# CONNECTEUR_3.net
KiCad netlist of a schematic drawn in Altium Designer
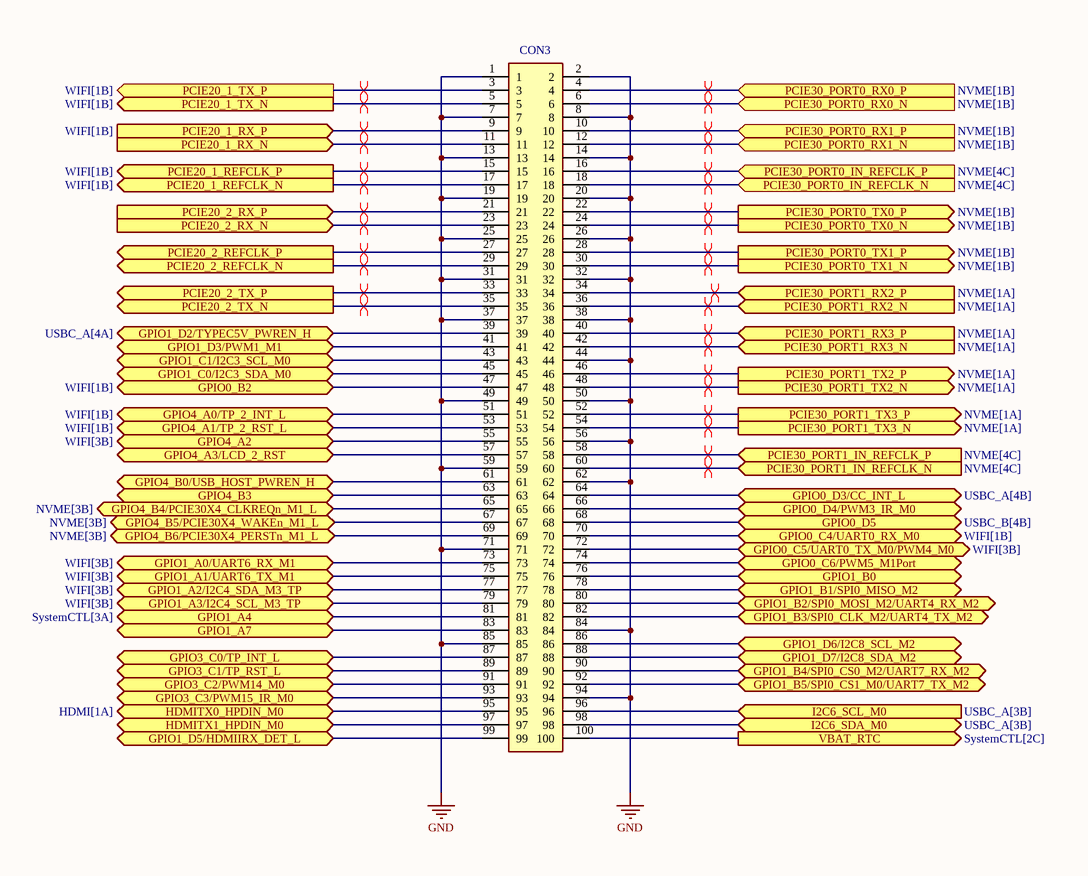
[diagram p0: CONNECTEUR_3.SchDoc, right]

(export (version "E")
  (design (tool "Eeschema 10.0.6"))
  (components
    (comp (ref "CON3")
      (value "DF40HC")
      (footprint "SamacSys:DF40HC30100DS04V51")
      (description "Stacking Board Connector, DF40 Series, Receptacle, 0.4 mm, 100, Surface Mount, G")
      (fields
        (field (name "MANUFACTURER_PART_NUMBER") "DF40HC(3.0)-100DS-0.4V(51")
        (field (name "MOUSER PART NUMBER") "798-DF40HC30100DS451")
      )
      (libsource (lib "SamacSys") (part "DF40HC(3.0)-100DS-0.4V(51)"))
    )
  )
  (nets
    (net (code "1") (name "/GPIO0_B2") (class "Default")
      (node (ref "CON3") (pin "47") (pinfunction "47_47") (pintype "passive"))
    )
    (net (code "2") (name "/GPIO0_C4{slash}UART0_RX_M0") (class "Default")
      (node (ref "CON3") (pin "70") (pinfunction "70_70") (pintype "passive"))
    )
    (net (code "3") (name "/GPIO0_C5{slash}UART0_TX_M0{slash}PWM4_M0") (class "Default")
      (node (ref "CON3") (pin "72") (pinfunction "72_72") (pintype "passive"))
    )
    (net (code "4") (name "/GPIO0_C6{slash}PWM5_M1Port") (class "Default")
      (node (ref "CON3") (pin "74") (pinfunction "74_74") (pintype "passive"))
    )
    (net (code "5") (name "/GPIO0_D3{slash}CC_INT_L") (class "Default")
      (node (ref "CON3") (pin "64") (pinfunction "64_64") (pintype "passive"))
    )
    (net (code "6") (name "/GPIO0_D4{slash}PWM3_IR_M0") (class "Default")
      (node (ref "CON3") (pin "66") (pinfunction "66_66") (pintype "passive"))
    )
    (net (code "7") (name "/GPIO0_D5") (class "Default")
      (node (ref "CON3") (pin "68") (pinfunction "68_68") (pintype "passive"))
    )
    (net (code "8") (name "/GPIO1_A0{slash}UART6_RX_M1") (class "Default")
      (node (ref "CON3") (pin "73") (pinfunction "73_73") (pintype "passive"))
    )
    (net (code "9") (name "/GPIO1_A1{slash}UART6_TX_M1") (class "Default")
      (node (ref "CON3") (pin "75") (pinfunction "75_75") (pintype "passive"))
    )
    (net (code "10") (name "/GPIO1_A2{slash}I2C4_SDA_M3_TP") (class "Default")
      (node (ref "CON3") (pin "77") (pinfunction "77_77") (pintype "passive"))
    )
    (net (code "11") (name "/GPIO1_A3{slash}I2C4_SCL_M3_TP") (class "Default")
      (node (ref "CON3") (pin "79") (pinfunction "79_79") (pintype "passive"))
    )
    (net (code "12") (name "/GPIO1_A4") (class "Default")
      (node (ref "CON3") (pin "81") (pinfunction "81_81") (pintype "passive"))
    )
    (net (code "13") (name "/GPIO1_A7") (class "Default")
      (node (ref "CON3") (pin "83") (pinfunction "83_83") (pintype "passive"))
    )
    (net (code "14") (name "/GPIO1_B0") (class "Default")
      (node (ref "CON3") (pin "76") (pinfunction "76_76") (pintype "passive"))
    )
    (net (code "15") (name "/GPIO1_B1{slash}SPI0_MISO_M2") (class "Default")
      (node (ref "CON3") (pin "78") (pinfunction "78_78") (pintype "passive"))
    )
    (net (code "16") (name "/GPIO1_B2{slash}SPI0_MOSI_M2{slash}UART4_RX_M2") (class "Default")
      (node (ref "CON3") (pin "80") (pinfunction "80_80") (pintype "passive"))
    )
    (net (code "17") (name "/GPIO1_B3{slash}SPI0_CLK_M2{slash}UART4_TX_M2") (class "Default")
      (node (ref "CON3") (pin "82") (pinfunction "82_82") (pintype "passive"))
    )
    (net (code "18") (name "/GPIO1_B4{slash}SPI0_CS0_M2{slash}UART7_RX_M2") (class "Default")
      (node (ref "CON3") (pin "90") (pinfunction "90_90") (pintype "passive"))
    )
    (net (code "19") (name "/GPIO1_B5{slash}SPI0_CS1_M0{slash}UART7_TX_M2") (class "Default")
      (node (ref "CON3") (pin "92") (pinfunction "92_92") (pintype "passive"))
    )
    (net (code "20") (name "/GPIO1_C0{slash}I2C3_SDA_M0") (class "Default")
      (node (ref "CON3") (pin "45") (pinfunction "45_45") (pintype "passive"))
    )
    (net (code "21") (name "/GPIO1_C1{slash}I2C3_SCL_M0") (class "Default")
      (node (ref "CON3") (pin "43") (pinfunction "43_43") (pintype "passive"))
    )
    (net (code "22") (name "/GPIO1_D2{slash}TYPEC5V_PWREN_H") (class "Default")
      (node (ref "CON3") (pin "39") (pinfunction "39_39") (pintype "passive"))
    )
    (net (code "23") (name "/GPIO1_D3{slash}PWM1_M1") (class "Default")
      (node (ref "CON3") (pin "41") (pinfunction "41_41") (pintype "passive"))
    )
    (net (code "24") (name "/GPIO1_D5{slash}HDMIIRX_DET_L") (class "Default")
      (node (ref "CON3") (pin "99") (pinfunction "99_99") (pintype "passive"))
    )
    (net (code "25") (name "/GPIO1_D6{slash}I2C8_SCL_M2") (class "Default")
      (node (ref "CON3") (pin "86") (pinfunction "86_86") (pintype "passive"))
    )
    (net (code "26") (name "/GPIO1_D7{slash}I2C8_SDA_M2") (class "Default")
      (node (ref "CON3") (pin "88") (pinfunction "88_88") (pintype "passive"))
    )
    (net (code "27") (name "/GPIO3_C0{slash}TP_INT_L") (class "Default")
      (node (ref "CON3") (pin "87") (pinfunction "87_87") (pintype "passive"))
    )
    (net (code "28") (name "/GPIO3_C1{slash}TP_RST_L") (class "Default")
      (node (ref "CON3") (pin "89") (pinfunction "89_89") (pintype "passive"))
    )
    (net (code "29") (name "/GPIO3_C2{slash}PWM14_M0") (class "Default")
      (node (ref "CON3") (pin "91") (pinfunction "91_91") (pintype "passive"))
    )
    (net (code "30") (name "/GPIO3_C3{slash}PWM15_IR_M0") (class "Default")
      (node (ref "CON3") (pin "93") (pinfunction "93_93") (pintype "passive"))
    )
    (net (code "31") (name "/GPIO4_A0{slash}TP_2_INT_L") (class "Default")
      (node (ref "CON3") (pin "51") (pinfunction "51_51") (pintype "passive"))
    )
    (net (code "32") (name "/GPIO4_A1{slash}TP_2_RST_L") (class "Default")
      (node (ref "CON3") (pin "53") (pinfunction "53_53") (pintype "passive"))
    )
    (net (code "33") (name "/GPIO4_A2") (class "Default")
      (node (ref "CON3") (pin "55") (pinfunction "55_55") (pintype "passive"))
    )
    (net (code "34") (name "/GPIO4_A3{slash}LCD_2_RST") (class "Default")
      (node (ref "CON3") (pin "57") (pinfunction "57_57") (pintype "passive"))
    )
    (net (code "35") (name "/GPIO4_B0{slash}USB_HOST_PWREN_H") (class "Default")
      (node (ref "CON3") (pin "61") (pinfunction "61_61") (pintype "passive"))
    )
    (net (code "36") (name "/GPIO4_B3") (class "Default")
      (node (ref "CON3") (pin "63") (pinfunction "63_63") (pintype "passive"))
    )
    (net (code "37") (name "/GPIO4_B4{slash}PCIE30X4_CLKREQn_M1_L") (class "Default")
      (node (ref "CON3") (pin "65") (pinfunction "65_65") (pintype "passive"))
    )
    (net (code "38") (name "/GPIO4_B5{slash}PCIE30X4_WAKEn_M1_L") (class "Default")
      (node (ref "CON3") (pin "67") (pinfunction "67_67") (pintype "passive"))
    )
    (net (code "39") (name "/GPIO4_B6{slash}PCIE30X4_PERSTn_M1_L") (class "Default")
      (node (ref "CON3") (pin "69") (pinfunction "69_69") (pintype "passive"))
    )
    (net (code "40") (name "/HDMITX0_HPDIN_M0") (class "Default")
      (node (ref "CON3") (pin "95") (pinfunction "95_95") (pintype "passive"))
    )
    (net (code "41") (name "/HDMITX1_HPDIN_M0") (class "Default")
      (node (ref "CON3") (pin "97") (pinfunction "97_97") (pintype "passive"))
    )
    (net (code "42") (name "/I2C6_SCL_M0") (class "Default")
      (node (ref "CON3") (pin "96") (pinfunction "96_96") (pintype "passive"))
    )
    (net (code "43") (name "/I2C6_SDA_M0") (class "Default")
      (node (ref "CON3") (pin "98") (pinfunction "98_98") (pintype "passive"))
    )
    (net (code "44") (name "/PCIE20_1_REFCLK_N") (class "Default")
      (node (ref "CON3") (pin "17") (pinfunction "17_17") (pintype "passive"))
    )
    (net (code "45") (name "/PCIE20_1_REFCLK_P") (class "Default")
      (node (ref "CON3") (pin "15") (pinfunction "15_15") (pintype "passive"))
    )
    (net (code "46") (name "/PCIE20_1_RX_N") (class "Default")
      (node (ref "CON3") (pin "11") (pinfunction "11_11") (pintype "passive"))
    )
    (net (code "47") (name "/PCIE20_1_RX_P") (class "Default")
      (node (ref "CON3") (pin "9") (pinfunction "9_9") (pintype "passive"))
    )
    (net (code "48") (name "/PCIE20_1_TX_N") (class "Default")
      (node (ref "CON3") (pin "5") (pinfunction "5_5") (pintype "passive"))
    )
    (net (code "49") (name "/PCIE20_1_TX_P") (class "Default")
      (node (ref "CON3") (pin "3") (pinfunction "3_3") (pintype "passive"))
    )
    (net (code "50") (name "/PCIE20_2_REFCLK_N") (class "Default")
      (node (ref "CON3") (pin "29") (pinfunction "29_29") (pintype "passive"))
    )
    (net (code "51") (name "/PCIE20_2_REFCLK_P") (class "Default")
      (node (ref "CON3") (pin "27") (pinfunction "27_27") (pintype "passive"))
    )
    (net (code "52") (name "/PCIE20_2_RX_N") (class "Default")
      (node (ref "CON3") (pin "23") (pinfunction "23_23") (pintype "passive"))
    )
    (net (code "53") (name "/PCIE20_2_RX_P") (class "Default")
      (node (ref "CON3") (pin "21") (pinfunction "21_21") (pintype "passive"))
    )
    (net (code "54") (name "/PCIE20_2_TX_N") (class "Default")
      (node (ref "CON3") (pin "35") (pinfunction "35_35") (pintype "passive"))
    )
    (net (code "55") (name "/PCIE20_2_TX_P") (class "Default")
      (node (ref "CON3") (pin "33") (pinfunction "33_33") (pintype "passive"))
    )
    (net (code "56") (name "/PCIE30_PORT0_IN_REFCLK_N") (class "Default")
      (node (ref "CON3") (pin "18") (pinfunction "18_18") (pintype "passive"))
    )
    (net (code "57") (name "/PCIE30_PORT0_IN_REFCLK_P") (class "Default")
      (node (ref "CON3") (pin "16") (pinfunction "16_16") (pintype "passive"))
    )
    (net (code "58") (name "/PCIE30_PORT0_RX0_N") (class "Default")
      (node (ref "CON3") (pin "6") (pinfunction "6_6") (pintype "passive"))
    )
    (net (code "59") (name "/PCIE30_PORT0_RX0_P") (class "Default")
      (node (ref "CON3") (pin "4") (pinfunction "4_4") (pintype "passive"))
    )
    (net (code "60") (name "/PCIE30_PORT0_RX1_N") (class "Default")
      (node (ref "CON3") (pin "12") (pinfunction "12_12") (pintype "passive"))
    )
    (net (code "61") (name "/PCIE30_PORT0_RX1_P") (class "Default")
      (node (ref "CON3") (pin "10") (pinfunction "10_10") (pintype "passive"))
    )
    (net (code "62") (name "/PCIE30_PORT0_TX0_N") (class "Default")
      (node (ref "CON3") (pin "24") (pinfunction "24_24") (pintype "passive"))
    )
    (net (code "63") (name "/PCIE30_PORT0_TX0_P") (class "Default")
      (node (ref "CON3") (pin "22") (pinfunction "22_22") (pintype "passive"))
    )
    (net (code "64") (name "/PCIE30_PORT0_TX1_N") (class "Default")
      (node (ref "CON3") (pin "30") (pinfunction "30_30") (pintype "passive"))
    )
    (net (code "65") (name "/PCIE30_PORT0_TX1_P") (class "Default")
      (node (ref "CON3") (pin "28") (pinfunction "28_28") (pintype "passive"))
    )
    (net (code "66") (name "/PCIE30_PORT1_IN_REFCLK_N") (class "Default")
      (node (ref "CON3") (pin "60") (pinfunction "60_60") (pintype "passive"))
    )
    (net (code "67") (name "/PCIE30_PORT1_IN_REFCLK_P") (class "Default")
      (node (ref "CON3") (pin "58") (pinfunction "58_58") (pintype "passive"))
    )
    (net (code "68") (name "/PCIE30_PORT1_RX2_N") (class "Default")
      (node (ref "CON3") (pin "36") (pinfunction "36_36") (pintype "passive"))
    )
    (net (code "69") (name "/PCIE30_PORT1_RX2_P") (class "Default")
      (node (ref "CON3") (pin "34") (pinfunction "34_34") (pintype "passive"))
    )
    (net (code "70") (name "/PCIE30_PORT1_RX3_N") (class "Default")
      (node (ref "CON3") (pin "42") (pinfunction "42_42") (pintype "passive"))
    )
    (net (code "71") (name "/PCIE30_PORT1_RX3_P") (class "Default")
      (node (ref "CON3") (pin "40") (pinfunction "40_40") (pintype "passive"))
    )
    (net (code "72") (name "/PCIE30_PORT1_TX2_N") (class "Default")
      (node (ref "CON3") (pin "48") (pinfunction "48_48") (pintype "passive"))
    )
    (net (code "73") (name "/PCIE30_PORT1_TX2_P") (class "Default")
      (node (ref "CON3") (pin "46") (pinfunction "46_46") (pintype "passive"))
    )
    (net (code "74") (name "/PCIE30_PORT1_TX3_N") (class "Default")
      (node (ref "CON3") (pin "54") (pinfunction "54_54") (pintype "passive"))
    )
    (net (code "75") (name "/PCIE30_PORT1_TX3_P") (class "Default")
      (node (ref "CON3") (pin "52") (pinfunction "52_52") (pintype "passive"))
    )
    (net (code "76") (name "/VBAT_RTC") (class "Default")
      (node (ref "CON3") (pin "100") (pinfunction "100_100") (pintype "passive"))
    )
    (net (code "77") (name "GND") (class "Default")
      (node (ref "CON3") (pin "1") (pinfunction "1_1") (pintype "passive"))
      (node (ref "CON3") (pin "13") (pinfunction "13_13") (pintype "passive"))
      (node (ref "CON3") (pin "14") (pinfunction "14_14") (pintype "passive"))
      (node (ref "CON3") (pin "19") (pinfunction "19_19") (pintype "passive"))
      (node (ref "CON3") (pin "2") (pinfunction "2_2") (pintype "passive"))
      (node (ref "CON3") (pin "20") (pinfunction "20_20") (pintype "passive"))
      (node (ref "CON3") (pin "25") (pinfunction "25_25") (pintype "passive"))
      (node (ref "CON3") (pin "26") (pinfunction "26_26") (pintype "passive"))
      (node (ref "CON3") (pin "31") (pinfunction "31_31") (pintype "passive"))
      (node (ref "CON3") (pin "32") (pinfunction "32_32") (pintype "passive"))
      (node (ref "CON3") (pin "37") (pinfunction "37_37") (pintype "passive"))
      (node (ref "CON3") (pin "38") (pinfunction "38_38") (pintype "passive"))
      (node (ref "CON3") (pin "44") (pinfunction "44_44") (pintype "passive"))
      (node (ref "CON3") (pin "49") (pinfunction "49_49") (pintype "passive"))
      (node (ref "CON3") (pin "50") (pinfunction "50_50") (pintype "passive"))
      (node (ref "CON3") (pin "56") (pinfunction "56_56") (pintype "passive"))
      (node (ref "CON3") (pin "59") (pinfunction "59_59") (pintype "passive"))
      (node (ref "CON3") (pin "62") (pinfunction "62_62") (pintype "passive"))
      (node (ref "CON3") (pin "7") (pinfunction "7_7") (pintype "passive"))
      (node (ref "CON3") (pin "71") (pinfunction "71_71") (pintype "passive"))
      (node (ref "CON3") (pin "8") (pinfunction "8_8") (pintype "passive"))
      (node (ref "CON3") (pin "84") (pinfunction "84_84") (pintype "passive"))
      (node (ref "CON3") (pin "85") (pinfunction "85_85") (pintype "passive"))
      (node (ref "CON3") (pin "94") (pinfunction "94_94") (pintype "passive"))
    )
  )
)
